# Main.net
KiCad netlist of a schematic drawn in Altium Designer
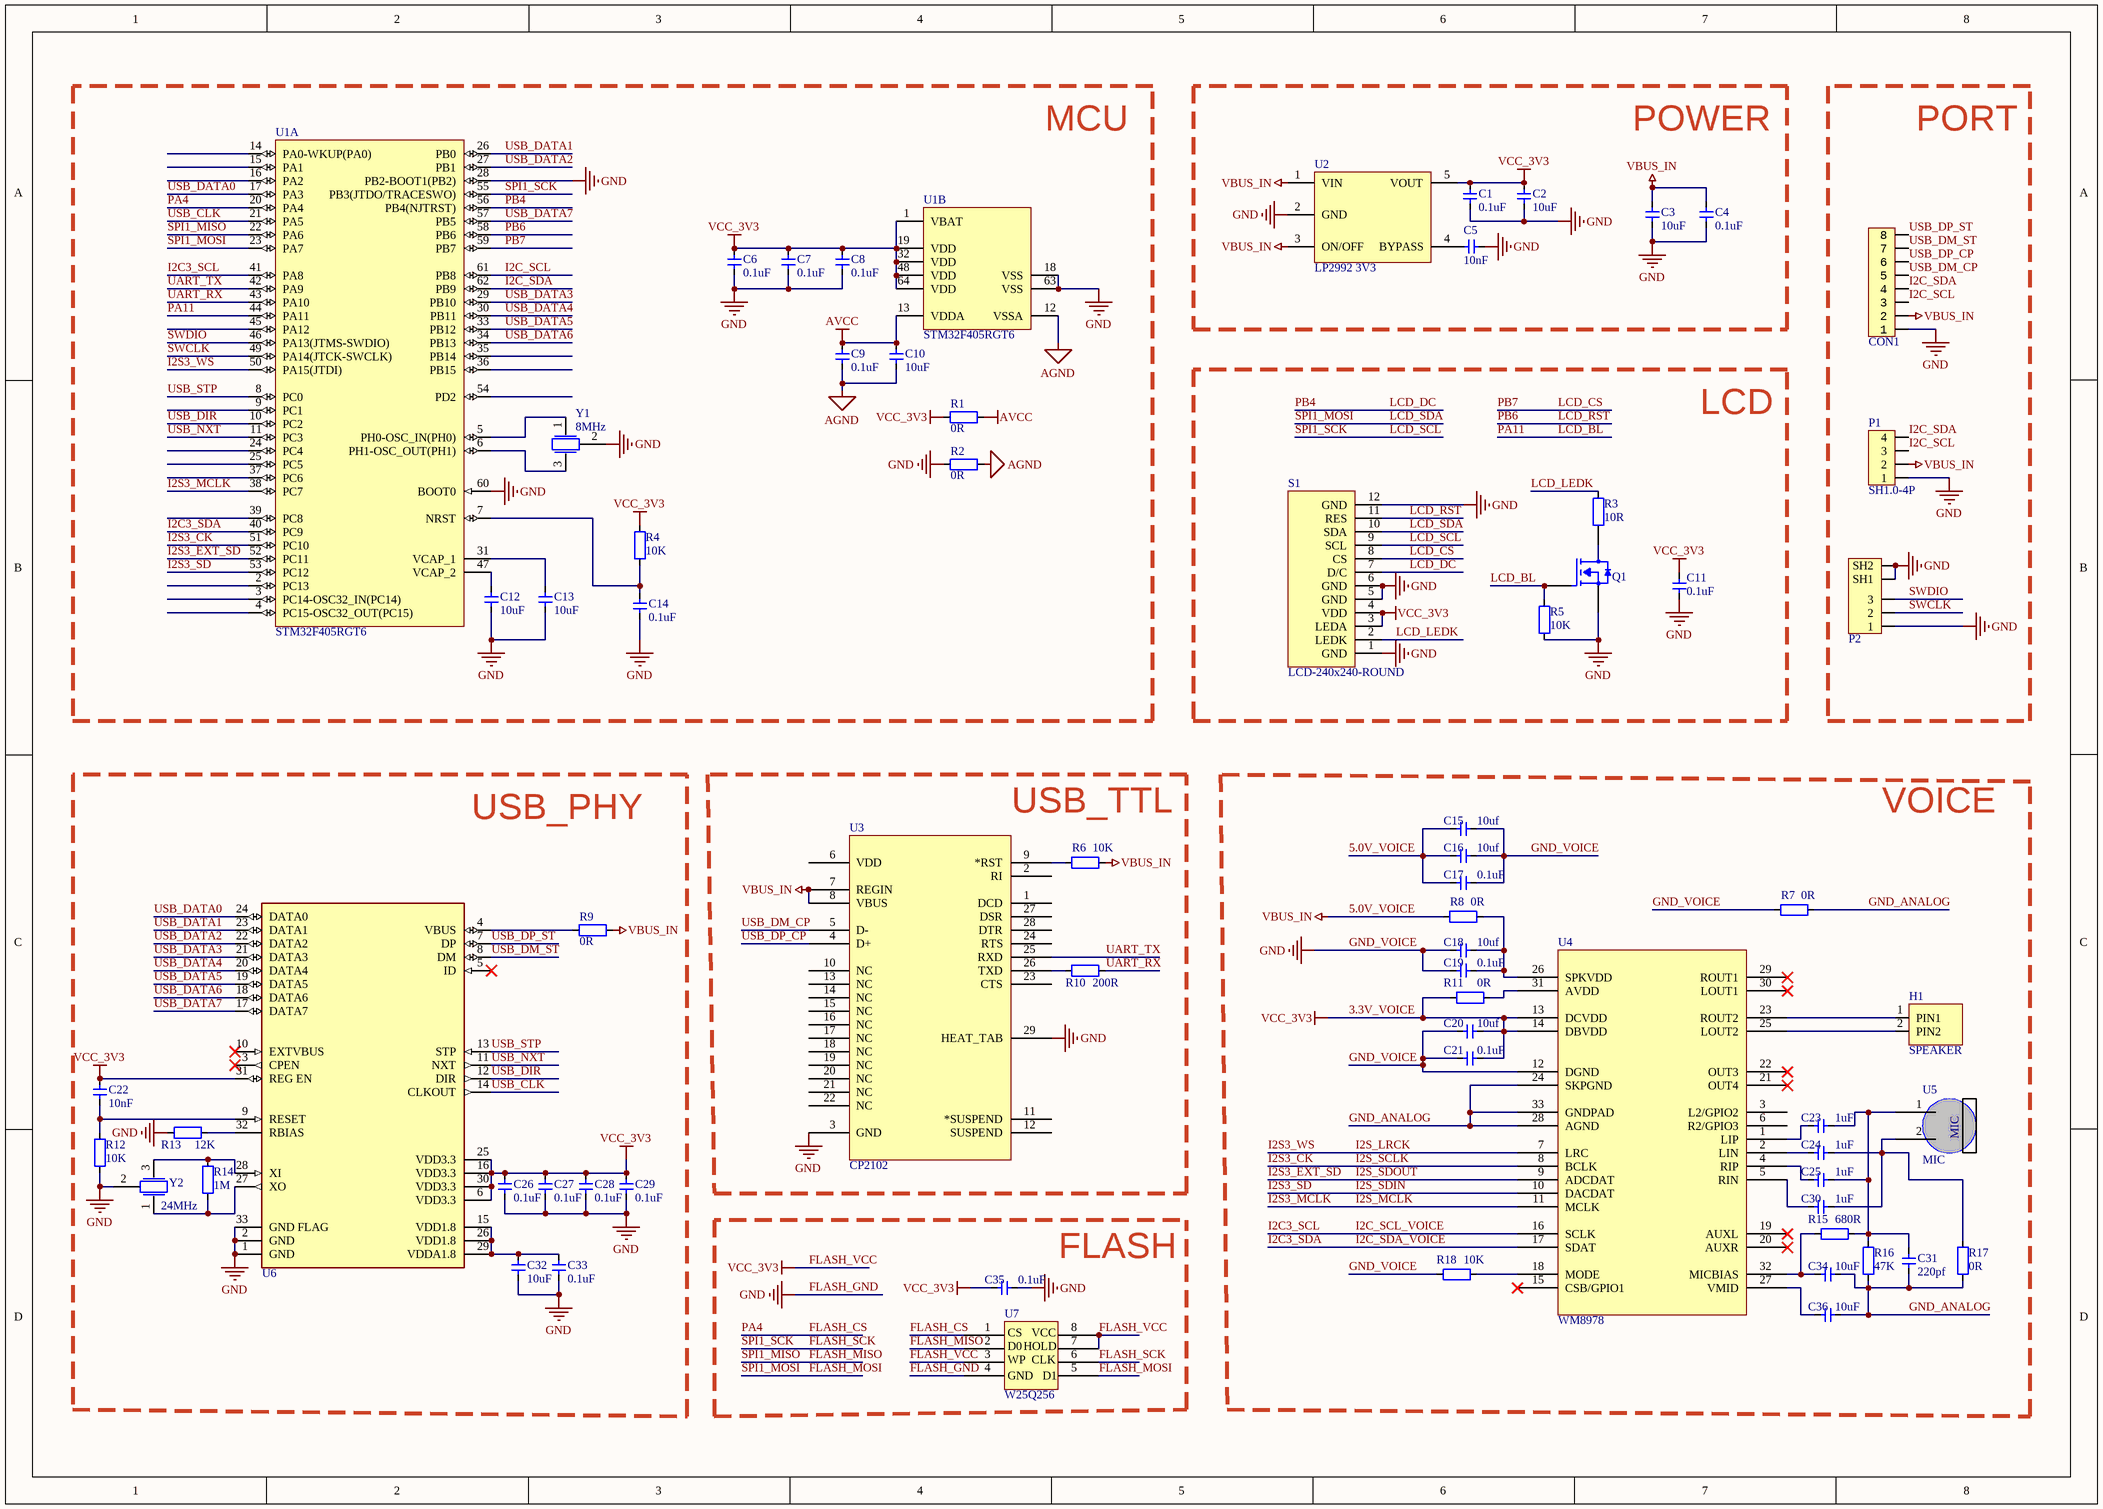
[diagram p0: Main.SchDoc]

(export (version "E")
  (design (tool "Eeschema 10.0.6"))
  (components
    (comp (ref "C1")
      (value "0.1uF")
      (footprint "ElectronBot:CAP_0402")
      (description "Capacitor")
      (libsource (lib "MyPcbLib") (part "电容-0402"))
    )
    (comp (ref "C2")
      (value "10uF")
      (footprint "ElectronBot:CAP_0402")
      (description "Capacitor")
      (libsource (lib "MyPcbLib") (part "电容-0402"))
    )
    (comp (ref "C3")
      (value "10uF")
      (footprint "ElectronBot:CAP_0402")
      (description "Capacitor")
      (libsource (lib "MyPcbLib") (part "电容-0402"))
    )
    (comp (ref "C4")
      (value "0.1uF")
      (footprint "ElectronBot:CAP_0402")
      (description "Capacitor")
      (libsource (lib "MyPcbLib") (part "电容-0402"))
    )
    (comp (ref "C5")
      (value "10nF")
      (footprint "ElectronBot:CAP_0402")
      (description "Capacitor")
      (libsource (lib "MyPcbLib") (part "电容-0402"))
    )
    (comp (ref "C6")
      (value "0.1uF")
      (footprint "ElectronBot:CAP_0402")
      (description "Capacitor")
      (libsource (lib "MyPcbLib") (part "电容-0402"))
    )
    (comp (ref "C7")
      (value "0.1uF")
      (footprint "ElectronBot:CAP_0402")
      (description "Capacitor")
      (libsource (lib "MyPcbLib") (part "电容-0402"))
    )
    (comp (ref "C8")
      (value "0.1uF")
      (footprint "ElectronBot:CAP_0402")
      (description "Capacitor")
      (libsource (lib "MyPcbLib") (part "电容-0402"))
    )
    (comp (ref "C9")
      (value "0.1uF")
      (footprint "ElectronBot:CAP_0402")
      (description "Capacitor")
      (libsource (lib "MyPcbLib") (part "电容-0402"))
    )
    (comp (ref "C10")
      (value "10uF")
      (footprint "ElectronBot:CAP_0402")
      (description "Capacitor")
      (libsource (lib "MyPcbLib") (part "电容-0402"))
    )
    (comp (ref "C11")
      (value "0.1uF")
      (footprint "ElectronBot:CAP_0402")
      (description "Capacitor")
      (libsource (lib "MyPcbLib") (part "电容-0402"))
    )
    (comp (ref "C12")
      (value "10uF")
      (footprint "ElectronBot:CAP_0402")
      (description "Capacitor")
      (libsource (lib "MyPcbLib") (part "电容-0402"))
    )
    (comp (ref "C13")
      (value "10uF")
      (footprint "ElectronBot:CAP_0402")
      (description "Capacitor")
      (libsource (lib "MyPcbLib") (part "电容-0402"))
    )
    (comp (ref "C14")
      (value "0.1uF")
      (footprint "ElectronBot:CAP_0402")
      (description "Capacitor")
      (libsource (lib "MyPcbLib") (part "电容-0402"))
    )
    (comp (ref "C15")
      (value "10uf")
      (footprint "ElectronBot:CAP_0402")
      (description "Capacitor")
      (libsource (lib "MyPcbLib") (part "电容-0402"))
    )
    (comp (ref "C16")
      (value "10uf")
      (footprint "ElectronBot:CAP_0402")
      (description "Capacitor")
      (libsource (lib "MyPcbLib") (part "电容-0402"))
    )
    (comp (ref "C17")
      (value "0.1uF")
      (footprint "ElectronBot:CAP_0402")
      (description "Capacitor")
      (libsource (lib "MyPcbLib") (part "电容-0402"))
    )
    (comp (ref "C18")
      (value "10uf")
      (footprint "ElectronBot:CAP_0402")
      (description "Capacitor")
      (libsource (lib "MyPcbLib") (part "电容-0402"))
    )
    (comp (ref "C19")
      (value "0.1uF")
      (footprint "ElectronBot:CAP_0402")
      (description "Capacitor")
      (libsource (lib "MyPcbLib") (part "电容-0402"))
    )
    (comp (ref "C20")
      (value "10uf")
      (footprint "ElectronBot:CAP_0402")
      (description "Capacitor")
      (libsource (lib "MyPcbLib") (part "电容-0402"))
    )
    (comp (ref "C21")
      (value "0.1uF")
      (footprint "ElectronBot:CAP_0402")
      (description "Capacitor")
      (libsource (lib "MyPcbLib") (part "电容-0402"))
    )
    (comp (ref "C22")
      (value "10nF")
      (footprint "ElectronBot:CAP_0402")
      (description "Capacitor")
      (libsource (lib "MyPcbLib") (part "电容-0402"))
    )
    (comp (ref "C23")
      (value "1uF")
      (footprint "ElectronBot:CAP_0402")
      (description "Capacitor")
      (libsource (lib "MyPcbLib") (part "电容-0402"))
    )
    (comp (ref "C24")
      (value "1uF")
      (footprint "ElectronBot:CAP_0402")
      (description "Capacitor")
      (libsource (lib "MyPcbLib") (part "电容-0402"))
    )
    (comp (ref "C25")
      (value "1uF")
      (footprint "ElectronBot:CAP_0402")
      (description "Capacitor")
      (libsource (lib "MyPcbLib") (part "电容-0402"))
    )
    (comp (ref "C26")
      (value "0.1uF")
      (footprint "ElectronBot:CAP_0402")
      (description "Capacitor")
      (libsource (lib "MyPcbLib") (part "电容-0402"))
    )
    (comp (ref "C27")
      (value "0.1uF")
      (footprint "ElectronBot:CAP_0402")
      (description "Capacitor")
      (libsource (lib "MyPcbLib") (part "电容-0402"))
    )
    (comp (ref "C28")
      (value "0.1uF")
      (footprint "ElectronBot:CAP_0402")
      (description "Capacitor")
      (libsource (lib "MyPcbLib") (part "电容-0402"))
    )
    (comp (ref "C29")
      (value "0.1uF")
      (footprint "ElectronBot:CAP_0402")
      (description "Capacitor")
      (libsource (lib "MyPcbLib") (part "电容-0402"))
    )
    (comp (ref "C30")
      (value "1uF")
      (footprint "ElectronBot:CAP_0402")
      (description "Capacitor")
      (libsource (lib "MyPcbLib") (part "电容-0402"))
    )
    (comp (ref "C31")
      (value "220pf")
      (footprint "ElectronBot:CAP_0402")
      (description "Capacitor")
      (libsource (lib "MyPcbLib") (part "电容-0402"))
    )
    (comp (ref "C32")
      (value "10uF")
      (footprint "ElectronBot:CAP_0402")
      (description "Capacitor")
      (libsource (lib "MyPcbLib") (part "电容-0402"))
    )
    (comp (ref "C33")
      (value "0.1uF")
      (footprint "ElectronBot:CAP_0402")
      (description "Capacitor")
      (libsource (lib "MyPcbLib") (part "电容-0402"))
    )
    (comp (ref "C34")
      (value "10uF")
      (footprint "ElectronBot:CAP_0402")
      (description "Capacitor")
      (libsource (lib "MyPcbLib") (part "电容-0402"))
    )
    (comp (ref "C35")
      (value "0.1uF")
      (footprint "ElectronBot:CAP_0402")
      (description "Capacitor")
      (libsource (lib "MyPcbLib") (part "电容-0402"))
    )
    (comp (ref "C36")
      (value "10uF")
      (footprint "ElectronBot:CAP_0402")
      (description "Capacitor")
      (libsource (lib "MyPcbLib") (part "电容-0402"))
    )
    (comp (ref "CON1")
      (value "FFC_0.5_8")
      (footprint "ElectronBot:FFC_0.5_8")
      (description "FFC")
      (libsource (lib "KitSprout") (part "FFC_0.5_8"))
    )
    (comp (ref "H1")
      (value "SPEAKER")
      (footprint "ElectronBot:header2p_1.0")
      (libsource (lib "MINI-copter") (part "HEADER-2P"))
    )
    (comp (ref "P1")
      (value "SH1.0-4P")
      (footprint "ElectronBot:SH1.0-4P")
      (libsource (lib "MyPcbLib") (part "SH1.0-4P"))
    )
    (comp (ref "P2")
      (value "SH1.0-3P-STAND")
      (footprint "ElectronBot:SH1.0-3P-STAND")
      (description "Header")
      (libsource (lib "MyPcbLib") (part "SH1.0-3P-STAND"))
    )
    (comp (ref "Q1")
      (value "AO3400A")
      (footprint "ElectronBot:SOT23-3")
      (description "N-MOS")
      (libsource (lib "MyPcbLib") (part "AO3400A"))
    )
    (comp (ref "R1")
      (value "0R")
      (footprint "ElectronBot:RES_0402")
      (description "Resistor")
      (libsource (lib "") (part "电阻-0402_1"))
    )
    (comp (ref "R2")
      (value "0R")
      (footprint "ElectronBot:RES_0402")
      (description "Resistor")
      (libsource (lib "") (part "电阻-0402_1"))
    )
    (comp (ref "R3")
      (value "10R")
      (footprint "ElectronBot:RES_0402")
      (description "Resistor")
      (libsource (lib "") (part "电阻-0402_2"))
    )
    (comp (ref "R4")
      (value "10K")
      (footprint "ElectronBot:RES_0402")
      (description "Resistor")
      (libsource (lib "") (part "电阻-0402_2"))
    )
    (comp (ref "R5")
      (value "10K")
      (footprint "ElectronBot:RES_0402")
      (description "Resistor")
      (libsource (lib "") (part "电阻-0402_2"))
    )
    (comp (ref "R6")
      (value "10K")
      (footprint "ElectronBot:RES_0402")
      (description "Resistor")
      (libsource (lib "") (part "电阻-0402_1"))
    )
    (comp (ref "R7")
      (value "0R")
      (footprint "ElectronBot:RES_0402")
      (description "Resistor")
      (libsource (lib "") (part "电阻-0402_1"))
    )
    (comp (ref "R8")
      (value "0R")
      (footprint "ElectronBot:RES_0402")
      (description "Resistor")
      (libsource (lib "") (part "电阻-0402_1"))
    )
    (comp (ref "R9")
      (value "0R")
      (footprint "ElectronBot:RES_0402")
      (description "Resistor")
      (libsource (lib "") (part "电阻-0402_1"))
    )
    (comp (ref "R10")
      (value "200R")
      (footprint "ElectronBot:RES_0402")
      (description "Resistor")
      (libsource (lib "") (part "电阻-0402_1"))
    )
    (comp (ref "R11")
      (value "0R")
      (footprint "ElectronBot:RES_0402")
      (description "Resistor")
      (libsource (lib "") (part "电阻-0402_1"))
    )
    (comp (ref "R12")
      (value "10K")
      (footprint "ElectronBot:RES_0402")
      (description "Resistor")
      (libsource (lib "MyPcbLib") (part "电阻-0402"))
    )
    (comp (ref "R13")
      (value "12K")
      (footprint "ElectronBot:RES_0402")
      (description "Resistor")
      (libsource (lib "") (part "电阻-0402_1"))
    )
    (comp (ref "R14")
      (value "1M")
      (footprint "ElectronBot:RES_0402")
      (description "Resistor")
      (libsource (lib "MyPcbLib") (part "电阻-0402"))
    )
    (comp (ref "R15")
      (value "680R")
      (footprint "ElectronBot:RES_0402")
      (description "Resistor")
      (libsource (lib "") (part "电阻-0402_1"))
    )
    (comp (ref "R16")
      (value "47K")
      (footprint "ElectronBot:RES_0402")
      (description "Resistor")
      (libsource (lib "MyPcbLib") (part "电阻-0402"))
    )
    (comp (ref "R17")
      (value "0R")
      (footprint "ElectronBot:RES_0402")
      (description "Resistor")
      (libsource (lib "MyPcbLib") (part "电阻-0402"))
    )
    (comp (ref "R18")
      (value "10K")
      (footprint "ElectronBot:RES_0402")
      (description "Resistor")
      (libsource (lib "") (part "电阻-0402_1"))
    )
    (comp (ref "S1")
      (value "LCD-240x240-ROUND")
      (footprint "ElectronBot:LCD-240x240-ROUND")
      (description "显示屏")
      (libsource (lib "mLib") (part "LCD-240x240-ROUND"))
    )
    (comp (ref "U1")
      (value "STM32F405RGT6")
      (footprint "ElectronBot:LQFP-64_N")
      (fields (field (name "MANUFACTURER") "STMicroelectronics"))
      (libsource (lib "STMicroelectronics STM32 F4") (part "STM32F405RGT6"))
    )
    (comp (ref "U2")
      (value "LP2992 3V3")
      (footprint "ElectronBot:SOT23-5")
      (description "LDO")
      (libsource (lib "MyPcbLib") (part "LP2992"))
    )
    (comp (ref "U3")
      (value "CP2102")
      (footprint "ElectronBot:QFN-28")
      (description "USB转TTL")
      (libsource (lib "mLib") (part "CP2102"))
    )
    (comp (ref "U4")
      (value "WM8978")
      (footprint "ElectronBot:QFN-32")
      (libsource (lib "voice") (part "WM8978"))
    )
    (comp (ref "U5") (value "MIC") (footprint "ElectronBot:MIC6*2.2") (libsource (lib "voice") (part "MIC")))
    (comp (ref "U6")
      (value "USB3300-EZK-TR")
      (footprint "ElectronBot:QFN-32")
      (libsource (lib "mLib") (part "USB3300-EZK-TR"))
    )
    (comp (ref "U7")
      (value "W25Q256")
      (footprint "ElectronBot:flash")
      (description "W25Q256-QFN8")
      (libsource (lib "New library") (part "W25Q256"))
    )
    (comp (ref "Y1")
      (value "8MHz")
      (footprint "ElectronBot:晶振-3P")
      (description "村田贴片")
      (libsource (lib "MyPcbLib") (part "晶振-3Pin"))
    )
    (comp (ref "Y2")
      (value "24MHz")
      (footprint "ElectronBot:晶振-3P")
      (description "村田贴片")
      (libsource (lib "MyPcbLib") (part "晶振-3Pin"))
    )
  )
  (nets
    (net (code "1") (name "/FLASH_CS") (class "Default")
      (node (ref "U1") (pin "20") (pinfunction "PA4_20") (pintype "bidirectional"))
      (node (ref "U7") (pin "1") (pinfunction "1_1") (pintype "passive"))
    )
    (net (code "2") (name "/FLASH_MISO") (class "Default")
      (node (ref "U1") (pin "22") (pinfunction "PA6_22") (pintype "bidirectional"))
      (node (ref "U7") (pin "2") (pinfunction "2_2") (pintype "passive"))
    )
    (net (code "3") (name "/FLASH_MOSI") (class "Default")
      (node (ref "S1") (pin "10") (pinfunction "SDA_10") (pintype "passive"))
      (node (ref "U1") (pin "23") (pinfunction "PA7_23") (pintype "bidirectional"))
      (node (ref "U7") (pin "5") (pinfunction "5_5") (pintype "passive"))
    )
    (net (code "4") (name "/FLASH_SCK") (class "Default")
      (node (ref "S1") (pin "9") (pinfunction "SCL_9") (pintype "passive"))
      (node (ref "U1") (pin "55") (pinfunction "PB3(JTDO/TRACESWO)_55") (pintype "bidirectional"))
      (node (ref "U7") (pin "6") (pinfunction "6_6") (pintype "passive"))
    )
    (net (code "5") (name "/GND_ANALOG") (class "Default")
      (node (ref "C31") (pin "1") (pinfunction "1_1") (pintype "passive"))
      (node (ref "C34") (pin "2") (pinfunction "2_2") (pintype "passive"))
      (node (ref "C36") (pin "2") (pinfunction "2_2") (pintype "passive"))
      (node (ref "R16") (pin "2") (pinfunction "2_2") (pintype "passive"))
      (node (ref "R17") (pin "2") (pinfunction "2_2") (pintype "passive"))
      (node (ref "R7") (pin "1") (pinfunction "1_1") (pintype "passive"))
      (node (ref "U4") (pin "24") (pinfunction "SKPGND_24") (pintype "passive"))
      (node (ref "U4") (pin "28") (pinfunction "AGND_28") (pintype "passive"))
      (node (ref "U4") (pin "33") (pinfunction "GNDPAD_33") (pintype "passive"))
    )
    (net (code "6") (name "/I2C3_SCL") (class "Default")
      (node (ref "U1") (pin "41") (pinfunction "PA8_41") (pintype "bidirectional"))
      (node (ref "U4") (pin "16") (pinfunction "SCLK_16") (pintype "passive"))
    )
    (net (code "7") (name "/I2C3_SDA") (class "Default")
      (node (ref "U1") (pin "40") (pinfunction "PC9_40") (pintype "bidirectional"))
      (node (ref "U4") (pin "17") (pinfunction "SDAT_17") (pintype "passive"))
    )
    (net (code "8") (name "/I2C_SCL") (class "Default")
      (node (ref "CON1") (pin "3") (pinfunction "3_3") (pintype "passive"))
      (node (ref "P1") (pin "3") (pinfunction "3_3") (pintype "passive"))
      (node (ref "U1") (pin "61") (pinfunction "PB8_61") (pintype "bidirectional"))
    )
    (net (code "9") (name "/I2C_SDA") (class "Default")
      (node (ref "CON1") (pin "4") (pinfunction "4_4") (pintype "passive"))
      (node (ref "P1") (pin "4") (pinfunction "4_4") (pintype "passive"))
      (node (ref "U1") (pin "62") (pinfunction "PB9_62") (pintype "bidirectional"))
    )
    (net (code "10") (name "/I2S3_CK") (class "Default")
      (node (ref "U1") (pin "51") (pinfunction "PC10_51") (pintype "bidirectional"))
      (node (ref "U4") (pin "8") (pinfunction "BCLK_8") (pintype "passive"))
    )
    (net (code "11") (name "/I2S3_EXT_SD") (class "Default")
      (node (ref "U1") (pin "52") (pinfunction "PC11_52") (pintype "bidirectional"))
      (node (ref "U4") (pin "9") (pinfunction "ADCDAT_9") (pintype "passive"))
    )
    (net (code "12") (name "/I2S3_MCLK") (class "Default")
      (node (ref "U1") (pin "38") (pinfunction "PC7_38") (pintype "bidirectional"))
      (node (ref "U4") (pin "11") (pinfunction "MCLK_11") (pintype "passive"))
    )
    (net (code "13") (name "/I2S3_SD") (class "Default")
      (node (ref "U1") (pin "53") (pinfunction "PC12_53") (pintype "bidirectional"))
      (node (ref "U4") (pin "10") (pinfunction "DACDAT_10") (pintype "passive"))
    )
    (net (code "14") (name "/I2S3_WS") (class "Default")
      (node (ref "U1") (pin "50") (pinfunction "PA15(JTDI)_50") (pintype "bidirectional"))
      (node (ref "U4") (pin "7") (pinfunction "LRC_7") (pintype "passive"))
    )
    (net (code "15") (name "/LCD_BL") (class "Default")
      (node (ref "Q1") (pin "1") (pinfunction "G_1") (pintype "passive"))
      (node (ref "R5") (pin "2") (pinfunction "2_2") (pintype "passive"))
      (node (ref "U1") (pin "44") (pinfunction "PA11_44") (pintype "bidirectional"))
    )
    (net (code "16") (name "/LCD_CS") (class "Default")
      (node (ref "S1") (pin "8") (pinfunction "CS_8") (pintype "passive"))
      (node (ref "U1") (pin "59") (pinfunction "PB7_59") (pintype "bidirectional"))
    )
    (net (code "17") (name "/LCD_DC") (class "Default")
      (node (ref "S1") (pin "7") (pinfunction "D/C_7") (pintype "passive"))
      (node (ref "U1") (pin "56") (pinfunction "PB4(NJTRST)_56") (pintype "bidirectional"))
    )
    (net (code "18") (name "/LCD_LEDK") (class "Default")
      (node (ref "R3") (pin "2") (pinfunction "2_2") (pintype "passive"))
      (node (ref "S1") (pin "2") (pinfunction "LEDK_2") (pintype "passive"))
    )
    (net (code "19") (name "/LCD_RST") (class "Default")
      (node (ref "S1") (pin "11") (pinfunction "RES_11") (pintype "passive"))
      (node (ref "U1") (pin "58") (pinfunction "PB6_58") (pintype "bidirectional"))
    )
    (net (code "20") (name "/SWCLK") (class "Default")
      (node (ref "P2") (pin "2") (pinfunction "2_2") (pintype "passive"))
      (node (ref "U1") (pin "49") (pinfunction "PA14(JTCK-SWCLK)_49") (pintype "bidirectional"))
    )
    (net (code "21") (name "/SWDIO") (class "Default")
      (node (ref "P2") (pin "3") (pinfunction "3_3") (pintype "passive"))
      (node (ref "U1") (pin "46") (pinfunction "PA13(JTMS-SWDIO)_46") (pintype "bidirectional"))
    )
    (net (code "22") (name "/UART_RX") (class "Default")
      (node (ref "R10") (pin "1") (pinfunction "1_1") (pintype "passive"))
      (node (ref "U1") (pin "43") (pinfunction "PA10_43") (pintype "bidirectional"))
    )
    (net (code "23") (name "/UART_TX") (class "Default")
      (node (ref "U1") (pin "42") (pinfunction "PA9_42") (pintype "bidirectional"))
      (node (ref "U3") (pin "25") (pinfunction "RXD_25") (pintype "passive"))
    )
    (net (code "24") (name "/USB_CLK") (class "Default")
      (node (ref "U1") (pin "21") (pinfunction "PA5_21") (pintype "bidirectional"))
      (node (ref "U6") (pin "14") (pinfunction "CLKOUT_14") (pintype "output"))
    )
    (net (code "25") (name "/USB_DATA0") (class "Default")
      (node (ref "U1") (pin "17") (pinfunction "PA3_17") (pintype "bidirectional"))
      (node (ref "U6") (pin "24") (pinfunction "DATA0_24") (pintype "bidirectional"))
    )
    (net (code "26") (name "/USB_DATA1") (class "Default")
      (node (ref "U1") (pin "26") (pinfunction "PB0_26") (pintype "bidirectional"))
      (node (ref "U6") (pin "23") (pinfunction "DATA1_23") (pintype "bidirectional"))
    )
    (net (code "27") (name "/USB_DATA2") (class "Default")
      (node (ref "U1") (pin "27") (pinfunction "PB1_27") (pintype "bidirectional"))
      (node (ref "U6") (pin "22") (pinfunction "DATA2_22") (pintype "bidirectional"))
    )
    (net (code "28") (name "/USB_DATA3") (class "Default")
      (node (ref "U1") (pin "29") (pinfunction "PB10_29") (pintype "bidirectional"))
      (node (ref "U6") (pin "21") (pinfunction "DATA3_21") (pintype "bidirectional"))
    )
    (net (code "29") (name "/USB_DATA4") (class "Default")
      (node (ref "U1") (pin "30") (pinfunction "PB11_30") (pintype "bidirectional"))
      (node (ref "U6") (pin "20") (pinfunction "DATA4_20") (pintype "bidirectional"))
    )
    (net (code "30") (name "/USB_DATA5") (class "Default")
      (node (ref "U1") (pin "33") (pinfunction "PB12_33") (pintype "bidirectional"))
      (node (ref "U6") (pin "19") (pinfunction "DATA5_19") (pintype "bidirectional"))
    )
    (net (code "31") (name "/USB_DATA6") (class "Default")
      (node (ref "U1") (pin "34") (pinfunction "PB13_34") (pintype "bidirectional"))
      (node (ref "U6") (pin "18") (pinfunction "DATA6_18") (pintype "bidirectional"))
    )
    (net (code "32") (name "/USB_DATA7") (class "Default")
      (node (ref "U1") (pin "57") (pinfunction "PB5_57") (pintype "bidirectional"))
      (node (ref "U6") (pin "17") (pinfunction "DATA7_17") (pintype "bidirectional"))
    )
    (net (code "33") (name "/USB_DIR") (class "Default")
      (node (ref "U1") (pin "10") (pinfunction "PC2_10") (pintype "bidirectional"))
      (node (ref "U6") (pin "12") (pinfunction "DIR_12") (pintype "output"))
    )
    (net (code "34") (name "/USB_DM_CP") (class "Default")
      (node (ref "CON1") (pin "5") (pinfunction "5_5") (pintype "passive"))
      (node (ref "U3") (pin "5") (pinfunction "D-_5") (pintype "passive"))
    )
    (net (code "35") (name "/USB_DM_ST") (class "Default")
      (node (ref "CON1") (pin "7") (pinfunction "7_7") (pintype "passive"))
      (node (ref "U6") (pin "8") (pinfunction "DM_8") (pintype "bidirectional"))
    )
    (net (code "36") (name "/USB_DP_CP") (class "Default")
      (node (ref "CON1") (pin "6") (pinfunction "6_6") (pintype "passive"))
      (node (ref "U3") (pin "4") (pinfunction "D+_4") (pintype "passive"))
    )
    (net (code "37") (name "/USB_DP_ST") (class "Default")
      (node (ref "CON1") (pin "8") (pinfunction "8_8") (pintype "passive"))
      (node (ref "U6") (pin "7") (pinfunction "DP_7") (pintype "bidirectional"))
    )
    (net (code "38") (name "/USB_NXT") (class "Default")
      (node (ref "U1") (pin "11") (pinfunction "PC3_11") (pintype "bidirectional"))
      (node (ref "U6") (pin "11") (pinfunction "NXT_11") (pintype "output"))
    )
    (net (code "39") (name "/USB_STP") (class "Default")
      (node (ref "U1") (pin "8") (pinfunction "PC0_8") (pintype "bidirectional"))
      (node (ref "U6") (pin "13") (pinfunction "STP_13") (pintype "input"))
    )
    (net (code "40") (name "AGND") (class "Default")
      (node (ref "C10") (pin "1") (pinfunction "1_1") (pintype "passive"))
      (node (ref "C9") (pin "1") (pinfunction "1_1") (pintype "passive"))
      (node (ref "R2") (pin "1") (pinfunction "1_1") (pintype "passive"))
      (node (ref "U1") (pin "12") (pinfunction "VSSA_12") (pintype "power_in"))
    )
    (net (code "41") (name "AVCC") (class "Default")
      (node (ref "C10") (pin "2") (pinfunction "2_2") (pintype "passive"))
      (node (ref "C9") (pin "2") (pinfunction "2_2") (pintype "passive"))
      (node (ref "R1") (pin "1") (pinfunction "1_1") (pintype "passive"))
      (node (ref "U1") (pin "13") (pinfunction "VDDA_13") (pintype "power_in"))
    )
    (net (code "42") (name "GND") (class "Default")
      (node (ref "C1") (pin "1") (pinfunction "1_1") (pintype "passive"))
      (node (ref "C11") (pin "1") (pinfunction "1_1") (pintype "passive"))
      (node (ref "C12") (pin "1") (pinfunction "1_1") (pintype "passive"))
      (node (ref "C13") (pin "1") (pinfunction "1_1") (pintype "passive"))
      (node (ref "C14") (pin "1") (pinfunction "1_1") (pintype "passive"))
      (node (ref "C15") (pin "2") (pinfunction "2_2") (pintype "passive"))
      (node (ref "C16") (pin "2") (pinfunction "2_2") (pintype "passive"))
      (node (ref "C17") (pin "2") (pinfunction "2_2") (pintype "passive"))
      (node (ref "C18") (pin "1") (pinfunction "1_1") (pintype "passive"))
      (node (ref "C19") (pin "1") (pinfunction "1_1") (pintype "passive"))
      (node (ref "C2") (pin "1") (pinfunction "1_1") (pintype "passive"))
      (node (ref "C20") (pin "1") (pinfunction "1_1") (pintype "passive"))
      (node (ref "C21") (pin "1") (pinfunction "1_1") (pintype "passive"))
      (node (ref "C26") (pin "2") (pinfunction "2_2") (pintype "passive"))
      (node (ref "C27") (pin "2") (pinfunction "2_2") (pintype "passive"))
      (node (ref "C28") (pin "2") (pinfunction "2_2") (pintype "passive"))
      (node (ref "C29") (pin "2") (pinfunction "2_2") (pintype "passive"))
      (node (ref "C3") (pin "1") (pinfunction "1_1") (pintype "passive"))
      (node (ref "C32") (pin "2") (pinfunction "2_2") (pintype "passive"))
      (node (ref "C33") (pin "2") (pinfunction "2_2") (pintype "passive"))
      (node (ref "C35") (pin "2") (pinfunction "2_2") (pintype "passive"))
      (node (ref "C4") (pin "1") (pinfunction "1_1") (pintype "passive"))
      (node (ref "C5") (pin "1") (pinfunction "1_1") (pintype "passive"))
      (node (ref "C6") (pin "1") (pinfunction "1_1") (pintype "passive"))
      (node (ref "C7") (pin "1") (pinfunction "1_1") (pintype "passive"))
      (node (ref "C8") (pin "1") (pinfunction "1_1") (pintype "passive"))
      (node (ref "CON1") (pin "1") (pinfunction "1_1") (pintype "passive"))
      (node (ref "P1") (pin "1") (pinfunction "1_1") (pintype "passive"))
      (node (ref "P2") (pin "1") (pinfunction "1_1") (pintype "passive"))
      (node (ref "P2") (pin "SH1") (pinfunction "SH1_SH1") (pintype "passive"))
      (node (ref "P2") (pin "SH2") (pinfunction "SH2_SH2") (pintype "passive"))
      (node (ref "Q1") (pin "2") (pinfunction "S_2") (pintype "passive"))
      (node (ref "R12") (pin "2") (pinfunction "2_2") (pintype "passive"))
      (node (ref "R13") (pin "2") (pinfunction "2_2") (pintype "passive"))
      (node (ref "R18") (pin "2") (pinfunction "2_2") (pintype "passive"))
      (node (ref "R2") (pin "2") (pinfunction "2_2") (pintype "passive"))
      (node (ref "R5") (pin "1") (pinfunction "1_1") (pintype "passive"))
      (node (ref "R7") (pin "2") (pinfunction "2_2") (pintype "passive"))
      (node (ref "S1") (pin "1") (pinfunction "GND_1") (pintype "passive"))
      (node (ref "S1") (pin "12") (pinfunction "GND_12") (pintype "passive"))
      (node (ref "S1") (pin "5") (pinfunction "GND_5") (pintype "passive"))
      (node (ref "S1") (pin "6") (pinfunction "GND_6") (pintype "passive"))
      (node (ref "U1") (pin "18") (pinfunction "VSS_18") (pintype "power_in"))
      (node (ref "U1") (pin "28") (pinfunction "PB2-BOOT1(PB2)_28") (pintype "bidirectional"))
      (node (ref "U1") (pin "60") (pinfunction "BOOT0_60") (pintype "input"))
      (node (ref "U1") (pin "63") (pinfunction "VSS_63") (pintype "power_in"))
      (node (ref "U2") (pin "2") (pinfunction "GND_2") (pintype "passive"))
      (node (ref "U3") (pin "29") (pinfunction "HEAT_TAB_29") (pintype "passive"))
      (node (ref "U3") (pin "3") (pinfunction "GND_3") (pintype "passive"))
      (node (ref "U4") (pin "12") (pinfunction "DGND_12") (pintype "passive"))
      (node (ref "U6") (pin "1") (pinfunction "GND_1") (pintype "power_in"))
      (node (ref "U6") (pin "2") (pinfunction "GND_2") (pintype "power_in"))
      (node (ref "U6") (pin "33") (pinfunction "GND_FLAG_33") (pintype "power_in"))
      (node (ref "U7") (pin "4") (pinfunction "4_4") (pintype "passive"))
      (node (ref "Y1") (pin "2") (pinfunction "2_2") (pintype "passive"))
      (node (ref "Y2") (pin "2") (pinfunction "2_2") (pintype "passive"))
    )
    (net (code "43") (name "Net-(C23-Pad2)") (class "Default")
      (node (ref "C23") (pin "2") (pinfunction "2_2") (pintype "passive"))
      (node (ref "C25") (pin "2") (pinfunction "2_2") (pintype "passive"))
      (node (ref "C31") (pin "2") (pinfunction "2_2") (pintype "passive"))
      (node (ref "R15") (pin "1") (pinfunction "1_1") (pintype "passive"))
      (node (ref "R16") (pin "1") (pinfunction "1_1") (pintype "passive"))
      (node (ref "U5") (pin "1") (pintype "passive"))
    )
    (net (code "44") (name "Net-(C24-Pad2)") (class "Default")
      (node (ref "C24") (pin "2") (pinfunction "2_2") (pintype "passive"))
      (node (ref "C30") (pin "2") (pinfunction "2_2") (pintype "passive"))
      (node (ref "R17") (pin "1") (pinfunction "1_1") (pintype "passive"))
      (node (ref "U5") (pin "2") (pintype "passive"))
    )
    (net (code "45") (name "Net-(H1-PIN1)") (class "Default")
      (node (ref "H1") (pin "1") (pinfunction "PIN1_1") (pintype "passive"))
      (node (ref "U4") (pin "23") (pinfunction "ROUT2_23") (pintype "passive"))
    )
    (net (code "46") (name "Net-(H1-PIN2)") (class "Default")
      (node (ref "H1") (pin "2") (pinfunction "PIN2_2") (pintype "passive"))
      (node (ref "U4") (pin "25") (pinfunction "LOUT2_25") (pintype "passive"))
    )
    (net (code "47") (name "Net-(Q1-D)") (class "Default")
      (node (ref "Q1") (pin "3") (pinfunction "D_3") (pintype "passive"))
      (node (ref "R3") (pin "1") (pinfunction "1_1") (pintype "passive"))
    )
    (net (code "48") (name "Net-(U1A-NRST)") (class "Default")
      (node (ref "C14") (pin "2") (pinfunction "2_2") (pintype "passive"))
      (node (ref "R4") (pin "1") (pinfunction "1_1") (pintype "passive"))
      (node (ref "U1") (pin "7") (pinfunction "NRST_7") (pintype "bidirectional"))
    )
    (net (code "49") (name "Net-(U1A-PH0-OSC_IN(PH0))") (class "Default")
      (node (ref "U1") (pin "5") (pinfunction "PH0-OSC_IN(PH0)_5") (pintype "bidirectional"))
      (node (ref "Y1") (pin "1") (pinfunction "1_1") (pintype "passive"))
    )
    (net (code "50") (name "Net-(U1A-PH1-OSC_OUT(PH1))") (class "Default")
      (node (ref "U1") (pin "6") (pinfunction "PH1-OSC_OUT(PH1)_6") (pintype "bidirectional"))
      (node (ref "Y1") (pin "3") (pinfunction "3_3") (pintype "passive"))
    )
    (net (code "51") (name "Net-(U1A-VCAP_1)") (class "Default")
      (node (ref "C13") (pin "2") (pinfunction "2_2") (pintype "passive"))
      (node (ref "U1") (pin "31") (pinfunction "VCAP_1_31") (pintype "power_in"))
    )
    (net (code "52") (name "Net-(U1A-VCAP_2)") (class "Default")
      (node (ref "C12") (pin "2") (pinfunction "2_2") (pintype "passive"))
      (node (ref "U1") (pin "47") (pinfunction "VCAP_2_47") (pintype "power_in"))
    )
    (net (code "53") (name "Net-(U2-BYPASS)") (class "Default")
      (node (ref "C5") (pin "2") (pinfunction "2_2") (pintype "passive"))
      (node (ref "U2") (pin "4") (pinfunction "BYPASS_4") (pintype "passive"))
    )
    (net (code "54") (name "Net-(U3-*RST)") (class "Default")
      (node (ref "R6") (pin "2") (pinfunction "2_2") (pintype "passive"))
      (node (ref "U3") (pin "9") (pinfunction "*RST_9") (pintype "passive"))
    )
    (net (code "55") (name "Net-(U3-TXD)") (class "Default")
      (node (ref "R10") (pin "2") (pinfunction "2_2") (pintype "passive"))
      (node (ref "U3") (pin "26") (pinfunction "TXD_26") (pintype "passive"))
    )
    (net (code "56") (name "Net-(U4-AVDD)") (class "Default")
      (node (ref "R11") (pin "1") (pinfunction "1_1") (pintype "passive"))
      (node (ref "U4") (pin "31") (pinfunction "AVDD_31") (pintype "passive"))
    )
    (net (code "57") (name "Net-(U4-LIN)") (class "Default")
      (node (ref "C24") (pin "1") (pinfunction "1_1") (pintype "passive"))
      (node (ref "U4") (pin "2") (pinfunction "LIN_2") (pintype "passive"))
    )
    (net (code "58") (name "Net-(U4-LIP)") (class "Default")
      (node (ref "C23") (pin "1") (pinfunction "1_1") (pintype "passive"))
      (node (ref "U4") (pin "1") (pinfunction "LIP_1") (pintype "passive"))
    )
    (net (code "59") (name "Net-(U4-MICBIAS)") (class "Default")
      (node (ref "C34") (pin "1") (pinfunction "1_1") (pintype "passive"))
      (node (ref "R15") (pin "2") (pinfunction "2_2") (pintype "passive"))
      (node (ref "U4") (pin "32") (pinfunction "MICBIAS_32") (pintype "passive"))
    )
    (net (code "60") (name "Net-(U4-MODE)") (class "Default")
      (node (ref "R18") (pin "1") (pinfunction "1_1") (pintype "passive"))
      (node (ref "U4") (pin "18") (pinfunction "MODE_18") (pintype "passive"))
    )
    (net (code "61") (name "Net-(U4-RIN)") (class "Default")
      (node (ref "C30") (pin "1") (pinfunction "1_1") (pintype "passive"))
      (node (ref "U4") (pin "5") (pinfunction "RIN_5") (pintype "passive"))
    )
    (net (code "62") (name "Net-(U4-RIP)") (class "Default")
      (node (ref "C25") (pin "1") (pinfunction "1_1") (pintype "passive"))
      (node (ref "U4") (pin "4") (pinfunction "RIP_4") (pintype "passive"))
    )
    (net (code "63") (name "Net-(U4-SPKVDD)") (class "Default")
      (node (ref "C18") (pin "2") (pinfunction "2_2") (pintype "passive"))
      (node (ref "C19") (pin "2") (pinfunction "2_2") (pintype "passive"))
      (node (ref "R8") (pin "1") (pinfunction "1_1") (pintype "passive"))
      (node (ref "U4") (pin "26") (pinfunction "SPKVDD_26") (pintype "passive"))
    )
    (net (code "64") (name "Net-(U4-VMID)") (class "Default")
      (node (ref "C36") (pin "1") (pinfunction "1_1") (pintype "passive"))
      (node (ref "U4") (pin "27") (pinfunction "VMID_27") (pintype "passive"))
    )
    (net (code "65") (name "Net-(U6-RBIAS)") (class "Default")
      (node (ref "R13") (pin "1") (pinfunction "1_1") (pintype "passive"))
      (node (ref "U6") (pin "32") (pinfunction "RBIAS_32") (pintype "power_in"))
    )
    (net (code "66") (name "Net-(U6-RESET)") (class "Default")
      (node (ref "C22") (pin "2") (pinfunction "2_2") (pintype "passive"))
      (node (ref "R12") (pin "1") (pinfunction "1_1") (pintype "passive"))
      (node (ref "U6") (pin "9") (pinfunction "RESET_9") (pintype "input"))
    )
    (net (code "67") (name "Net-(U6-VBUS)") (class "Default")
      (node (ref "R9") (pin "2") (pinfunction "2_2") (pintype "passive"))
      (node (ref "U6") (pin "4") (pinfunction "VBUS_4") (pintype "bidirectional"))
    )
    (net (code "68") (name "Net-(U6-VDDA1.8)") (class "Default")
      (node (ref "C32") (pin "1") (pinfunction "1_1") (pintype "passive"))
      (node (ref "C33") (pin "1") (pinfunction "1_1") (pintype "passive"))
      (node (ref "U6") (pin "15") (pinfunction "VDD1.8_15") (pintype "power_in"))
      (node (ref "U6") (pin "26") (pinfunction "VDD1.8_26") (pintype "power_in"))
      (node (ref "U6") (pin "29") (pinfunction "VDDA1.8_29") (pintype "power_in"))
    )
    (net (code "69") (name "Net-(U6-XI)") (class "Default")
      (node (ref "R14") (pin "1") (pinfunction "1_1") (pintype "passive"))
      (node (ref "U6") (pin "28") (pinfunction "XI_28") (pintype "input"))
      (node (ref "Y2") (pin "3") (pinfunction "3_3") (pintype "passive"))
    )
    (net (code "70") (name "Net-(U6-XO)") (class "Default")
      (node (ref "R14") (pin "2") (pinfunction "2_2") (pintype "passive"))
      (node (ref "U6") (pin "27") (pinfunction "XO_27") (pintype "output"))
      (node (ref "Y2") (pin "1") (pinfunction "1_1") (pintype "passive"))
    )
    (net (code "71") (name "VBUS_IN") (class "Default")
      (node (ref "C15") (pin "1") (pinfunction "1_1") (pintype "passive"))
      (node (ref "C16") (pin "1") (pinfunction "1_1") (pintype "passive"))
      (node (ref "C17") (pin "1") (pinfunction "1_1") (pintype "passive"))
      (node (ref "C3") (pin "2") (pinfunction "2_2") (pintype "passive"))
      (node (ref "C4") (pin "2") (pinfunction "2_2") (pintype "passive"))
      (node (ref "CON1") (pin "2") (pinfunction "2_2") (pintype "passive"))
      (node (ref "P1") (pin "2") (pinfunction "2_2") (pintype "passive"))
      (node (ref "R6") (pin "1") (pinfunction "1_1") (pintype "passive"))
      (node (ref "R8") (pin "2") (pinfunction "2_2") (pintype "passive"))
      (node (ref "R9") (pin "1") (pinfunction "1_1") (pintype "passive"))
      (node (ref "U2") (pin "1") (pinfunction "VIN_1") (pintype "passive"))
      (node (ref "U2") (pin "3") (pinfunction "ON/OFF_3") (pintype "passive"))
      (node (ref "U3") (pin "7") (pinfunction "REGIN_7") (pintype "passive"))
      (node (ref "U3") (pin "8") (pinfunction "VBUS_8") (pintype "passive"))
    )
    (net (code "72") (name "VCC_3V3") (class "Default")
      (node (ref "C1") (pin "2") (pinfunction "2_2") (pintype "passive"))
      (node (ref "C11") (pin "2") (pinfunction "2_2") (pintype "passive"))
      (node (ref "C2") (pin "2") (pinfunction "2_2") (pintype "passive"))
      (node (ref "C20") (pin "2") (pinfunction "2_2") (pintype "passive"))
      (node (ref "C21") (pin "2") (pinfunction "2_2") (pintype "passive"))
      (node (ref "C22") (pin "1") (pinfunction "1_1") (pintype "passive"))
      (node (ref "C26") (pin "1") (pinfunction "1_1") (pintype "passive"))
      (node (ref "C27") (pin "1") (pinfunction "1_1") (pintype "passive"))
      (node (ref "C28") (pin "1") (pinfunction "1_1") (pintype "passive"))
      (node (ref "C29") (pin "1") (pinfunction "1_1") (pintype "passive"))
      (node (ref "C35") (pin "1") (pinfunction "1_1") (pintype "passive"))
      (node (ref "C6") (pin "2") (pinfunction "2_2") (pintype "passive"))
      (node (ref "C7") (pin "2") (pinfunction "2_2") (pintype "passive"))
      (node (ref "C8") (pin "2") (pinfunction "2_2") (pintype "passive"))
      (node (ref "R1") (pin "2") (pinfunction "2_2") (pintype "passive"))
      (node (ref "R11") (pin "2") (pinfunction "2_2") (pintype "passive"))
      (node (ref "R4") (pin "2") (pinfunction "2_2") (pintype "passive"))
      (node (ref "S1") (pin "3") (pinfunction "LEDA_3") (pintype "passive"))
      (node (ref "S1") (pin "4") (pinfunction "VDD_4") (pintype "passive"))
      (node (ref "U1") (pin "1") (pinfunction "VBAT_1") (pintype "power_in"))
      (node (ref "U1") (pin "19") (pinfunction "VDD_19") (pintype "power_in"))
      (node (ref "U1") (pin "32") (pinfunction "VDD_32") (pintype "power_in"))
      (node (ref "U1") (pin "48") (pinfunction "VDD_48") (pintype "power_in"))
      (node (ref "U1") (pin "64") (pinfunction "VDD_64") (pintype "power_in"))
      (node (ref "U2") (pin "5") (pinfunction "VOUT_5") (pintype "passive"))
      (node (ref "U4") (pin "13") (pinfunction "DCVDD_13") (pintype "passive"))
      (node (ref "U4") (pin "14") (pinfunction "DBVDD_14") (pintype "passive"))
      (node (ref "U6") (pin "16") (pinfunction "VDD3.3_16") (pintype "power_in"))
      (node (ref "U6") (pin "25") (pinfunction "VDD3.3_25") (pintype "power_in"))
      (node (ref "U6") (pin "30") (pinfunction "VDD3.3_30") (pintype "power_in"))
      (node (ref "U6") (pin "31") (pinfunction "REG_EN_31") (pintype "bidirectional"))
      (node (ref "U6") (pin "6") (pinfunction "VDD3.3_6") (pintype "power_in"))
      (node (ref "U7") (pin "3") (pinfunction "3_3") (pintype "passive"))
      (node (ref "U7") (pin "7") (pinfunction "7_7") (pintype "passive"))
      (node (ref "U7") (pin "8") (pinfunction "8_8") (pintype "passive"))
    )
    (net (code "73") (name "unconnected-(U1A-PA0-WKUP(PA0)-Pad14)") (class "Default")
      (node (ref "U1") (pin "14") (pinfunction "PA0-WKUP(PA0)_14") (pintype "bidirectional"))
    )
    (net (code "74") (name "unconnected-(U1A-PA1-Pad15)") (class "Default")
      (node (ref "U1") (pin "15") (pinfunction "PA1_15") (pintype "bidirectional"))
    )
    (net (code "75") (name "unconnected-(U1A-PA2-Pad16)") (class "Default")
      (node (ref "U1") (pin "16") (pinfunction "PA2_16") (pintype "bidirectional"))
    )
    (net (code "76") (name "unconnected-(U1A-PA12-Pad45)") (class "Default")
      (node (ref "U1") (pin "45") (pinfunction "PA12_45") (pintype "bidirectional"))
    )
    (net (code "77") (name "unconnected-(U1A-PB14-Pad35)") (class "Default")
      (node (ref "U1") (pin "35") (pinfunction "PB14_35") (pintype "bidirectional"))
    )
    (net (code "78") (name "unconnected-(U1A-PB15-Pad36)") (class "Default")
      (node (ref "U1") (pin "36") (pinfunction "PB15_36") (pintype "bidirectional"))
    )
    (net (code "79") (name "unconnected-(U1A-PC1-Pad9)") (class "Default")
      (node (ref "U1") (pin "9") (pinfunction "PC1_9") (pintype "bidirectional"))
    )
    (net (code "80") (name "unconnected-(U1A-PC4-Pad24)") (class "Default")
      (node (ref "U1") (pin "24") (pinfunction "PC4_24") (pintype "bidirectional"))
    )
    (net (code "81") (name "unconnected-(U1A-PC5-Pad25)") (class "Default")
      (node (ref "U1") (pin "25") (pinfunction "PC5_25") (pintype "bidirectional"))
    )
    (net (code "82") (name "unconnected-(U1A-PC6-Pad37)") (class "Default")
      (node (ref "U1") (pin "37") (pinfunction "PC6_37") (pintype "bidirectional"))
    )
    (net (code "83") (name "unconnected-(U1A-PC8-Pad39)") (class "Default")
      (node (ref "U1") (pin "39") (pinfunction "PC8_39") (pintype "bidirectional"))
    )
    (net (code "84") (name "unconnected-(U1A-PC13-Pad2)") (class "Default")
      (node (ref "U1") (pin "2") (pinfunction "PC13_2") (pintype "bidirectional"))
    )
    (net (code "85") (name "unconnected-(U1A-PC14-OSC32_IN(PC14)-Pad3)") (class "Default")
      (node (ref "U1") (pin "3") (pinfunction "PC14-OSC32_IN(PC14)_3") (pintype "bidirectional"))
    )
    (net (code "86") (name "unconnected-(U1A-PC15-OSC32_OUT(PC15)-Pad4)") (class "Default")
      (node (ref "U1") (pin "4") (pinfunction "PC15-OSC32_OUT(PC15)_4") (pintype "bidirectional"))
    )
    (net (code "87") (name "unconnected-(U1A-PD2-Pad54)") (class "Default")
      (node (ref "U1") (pin "54") (pinfunction "PD2_54") (pintype "bidirectional"))
    )
    (net (code "88") (name "unconnected-(U3-*SUSPEND-Pad11)") (class "Default")
      (node (ref "U3") (pin "11") (pinfunction "*SUSPEND_11") (pintype "passive"))
    )
    (net (code "89") (name "unconnected-(U3-CTS-Pad23)") (class "Default")
      (node (ref "U3") (pin "23") (pinfunction "CTS_23") (pintype "passive"))
    )
    (net (code "90") (name "unconnected-(U3-DCD-Pad1)") (class "Default")
      (node (ref "U3") (pin "1") (pinfunction "DCD_1") (pintype "passive"))
    )
    (net (code "91") (name "unconnected-(U3-DSR-Pad27)") (class "Default")
      (node (ref "U3") (pin "27") (pinfunction "DSR_27") (pintype "passive"))
    )
    (net (code "92") (name "unconnected-(U3-DTR-Pad28)") (class "Default")
      (node (ref "U3") (pin "28") (pinfunction "DTR_28") (pintype "passive"))
    )
    (net (code "93") (name "unconnected-(U3-NC-Pad10)") (class "Default")
      (node (ref "U3") (pin "10") (pinfunction "NC_10") (pintype "passive"))
    )
    (net (code "94") (name "unconnected-(U3-NC-Pad13)") (class "Default")
      (node (ref "U3") (pin "13") (pinfunction "NC_13") (pintype "passive"))
    )
    (net (code "95") (name "unconnected-(U3-NC-Pad14)") (class "Default")
      (node (ref "U3") (pin "14") (pinfunction "NC_14") (pintype "passive"))
    )
    (net (code "96") (name "unconnected-(U3-NC-Pad15)") (class "Default")
      (node (ref "U3") (pin "15") (pinfunction "NC_15") (pintype "passive"))
    )
    (net (code "97") (name "unconnected-(U3-NC-Pad16)") (class "Default")
      (node (ref "U3") (pin "16") (pinfunction "NC_16") (pintype "passive"))
    )
    (net (code "98") (name "unconnected-(U3-NC-Pad17)") (class "Default")
      (node (ref "U3") (pin "17") (pinfunction "NC_17") (pintype "passive"))
    )
    (net (code "99") (name "unconnected-(U3-NC-Pad18)") (class "Default")
      (node (ref "U3") (pin "18") (pinfunction "NC_18") (pintype "passive"))
    )
    (net (code "100") (name "unconnected-(U3-NC-Pad19)") (class "Default")
      (node (ref "U3") (pin "19") (pinfunction "NC_19") (pintype "passive"))
    )
    (net (code "101") (name "unconnected-(U3-NC-Pad20)") (class "Default")
      (node (ref "U3") (pin "20") (pinfunction "NC_20") (pintype "passive"))
    )
    (net (code "102") (name "unconnected-(U3-NC-Pad21)") (class "Default")
      (node (ref "U3") (pin "21") (pinfunction "NC_21") (pintype "passive"))
    )
    (net (code "103") (name "unconnected-(U3-NC-Pad22)") (class "Default")
      (node (ref "U3") (pin "22") (pinfunction "NC_22") (pintype "passive"))
    )
    (net (code "104") (name "unconnected-(U3-RI-Pad2)") (class "Default")
      (node (ref "U3") (pin "2") (pinfunction "RI_2") (pintype "passive"))
    )
    (net (code "105") (name "unconnected-(U3-RTS-Pad24)") (class "Default")
      (node (ref "U3") (pin "24") (pinfunction "RTS_24") (pintype "passive"))
    )
    (net (code "106") (name "unconnected-(U3-SUSPEND-Pad12)") (class "Default")
      (node (ref "U3") (pin "12") (pinfunction "SUSPEND_12") (pintype "passive"))
    )
    (net (code "107") (name "unconnected-(U3-VDD-Pad6)") (class "Default")
      (node (ref "U3") (pin "6") (pinfunction "VDD_6") (pintype "passive"))
    )
    (net (code "108") (name "unconnected-(U4-AUXL-Pad19)") (class "Default")
      (node (ref "U4") (pin "19") (pinfunction "AUXL_19") (pintype "passive+no_connect"))
    )
    (net (code "109") (name "unconnected-(U4-AUXR-Pad20)") (class "Default")
      (node (ref "U4") (pin "20") (pinfunction "AUXR_20") (pintype "passive+no_connect"))
    )
    (net (code "110") (name "unconnected-(U4-CSB{slash}GPIO1-Pad15)") (class "Default")
      (node (ref "U4") (pin "15") (pinfunction "CSB/GPIO1_15") (pintype "passive+no_connect"))
    )
    (net (code "111") (name "unconnected-(U4-L2{slash}GPIO2-Pad3)") (class "Default")
      (node (ref "U4") (pin "3") (pinfunction "L2/GPIO2_3") (pintype "passive"))
    )
    (net (code "112") (name "unconnected-(U4-LOUT1-Pad30)") (class "Default")
      (node (ref "U4") (pin "30") (pinfunction "LOUT1_30") (pintype "passive+no_connect"))
    )
    (net (code "113") (name "unconnected-(U4-OUT3-Pad22)") (class "Default")
      (node (ref "U4") (pin "22") (pinfunction "OUT3_22") (pintype "passive+no_connect"))
    )
    (net (code "114") (name "unconnected-(U4-OUT4-Pad21)") (class "Default")
      (node (ref "U4") (pin "21") (pinfunction "OUT4_21") (pintype "passive+no_connect"))
    )
    (net (code "115") (name "unconnected-(U4-R2{slash}GPIO3-Pad6)") (class "Default")
      (node (ref "U4") (pin "6") (pinfunction "R2/GPIO3_6") (pintype "passive"))
    )
    (net (code "116") (name "unconnected-(U4-ROUT1-Pad29)") (class "Default")
      (node (ref "U4") (pin "29") (pinfunction "ROUT1_29") (pintype "passive+no_connect"))
    )
    (net (code "117") (name "unconnected-(U6-CPEN-Pad3)") (class "Default")
      (node (ref "U6") (pin "3") (pinfunction "CPEN_3") (pintype "output+no_connect"))
    )
    (net (code "118") (name "unconnected-(U6-EXTVBUS-Pad10)") (class "Default")
      (node (ref "U6") (pin "10") (pinfunction "EXTVBUS_10") (pintype "input+no_connect"))
    )
    (net (code "119") (name "unconnected-(U6-ID-Pad5)") (class "Default")
      (node (ref "U6") (pin "5") (pinfunction "ID_5") (pintype "input+no_connect"))
    )
  )
)
